# ProDoc_Board1_2026-04-23.net
KiCad netlist of a schematic drawn in EasyEDA Pro
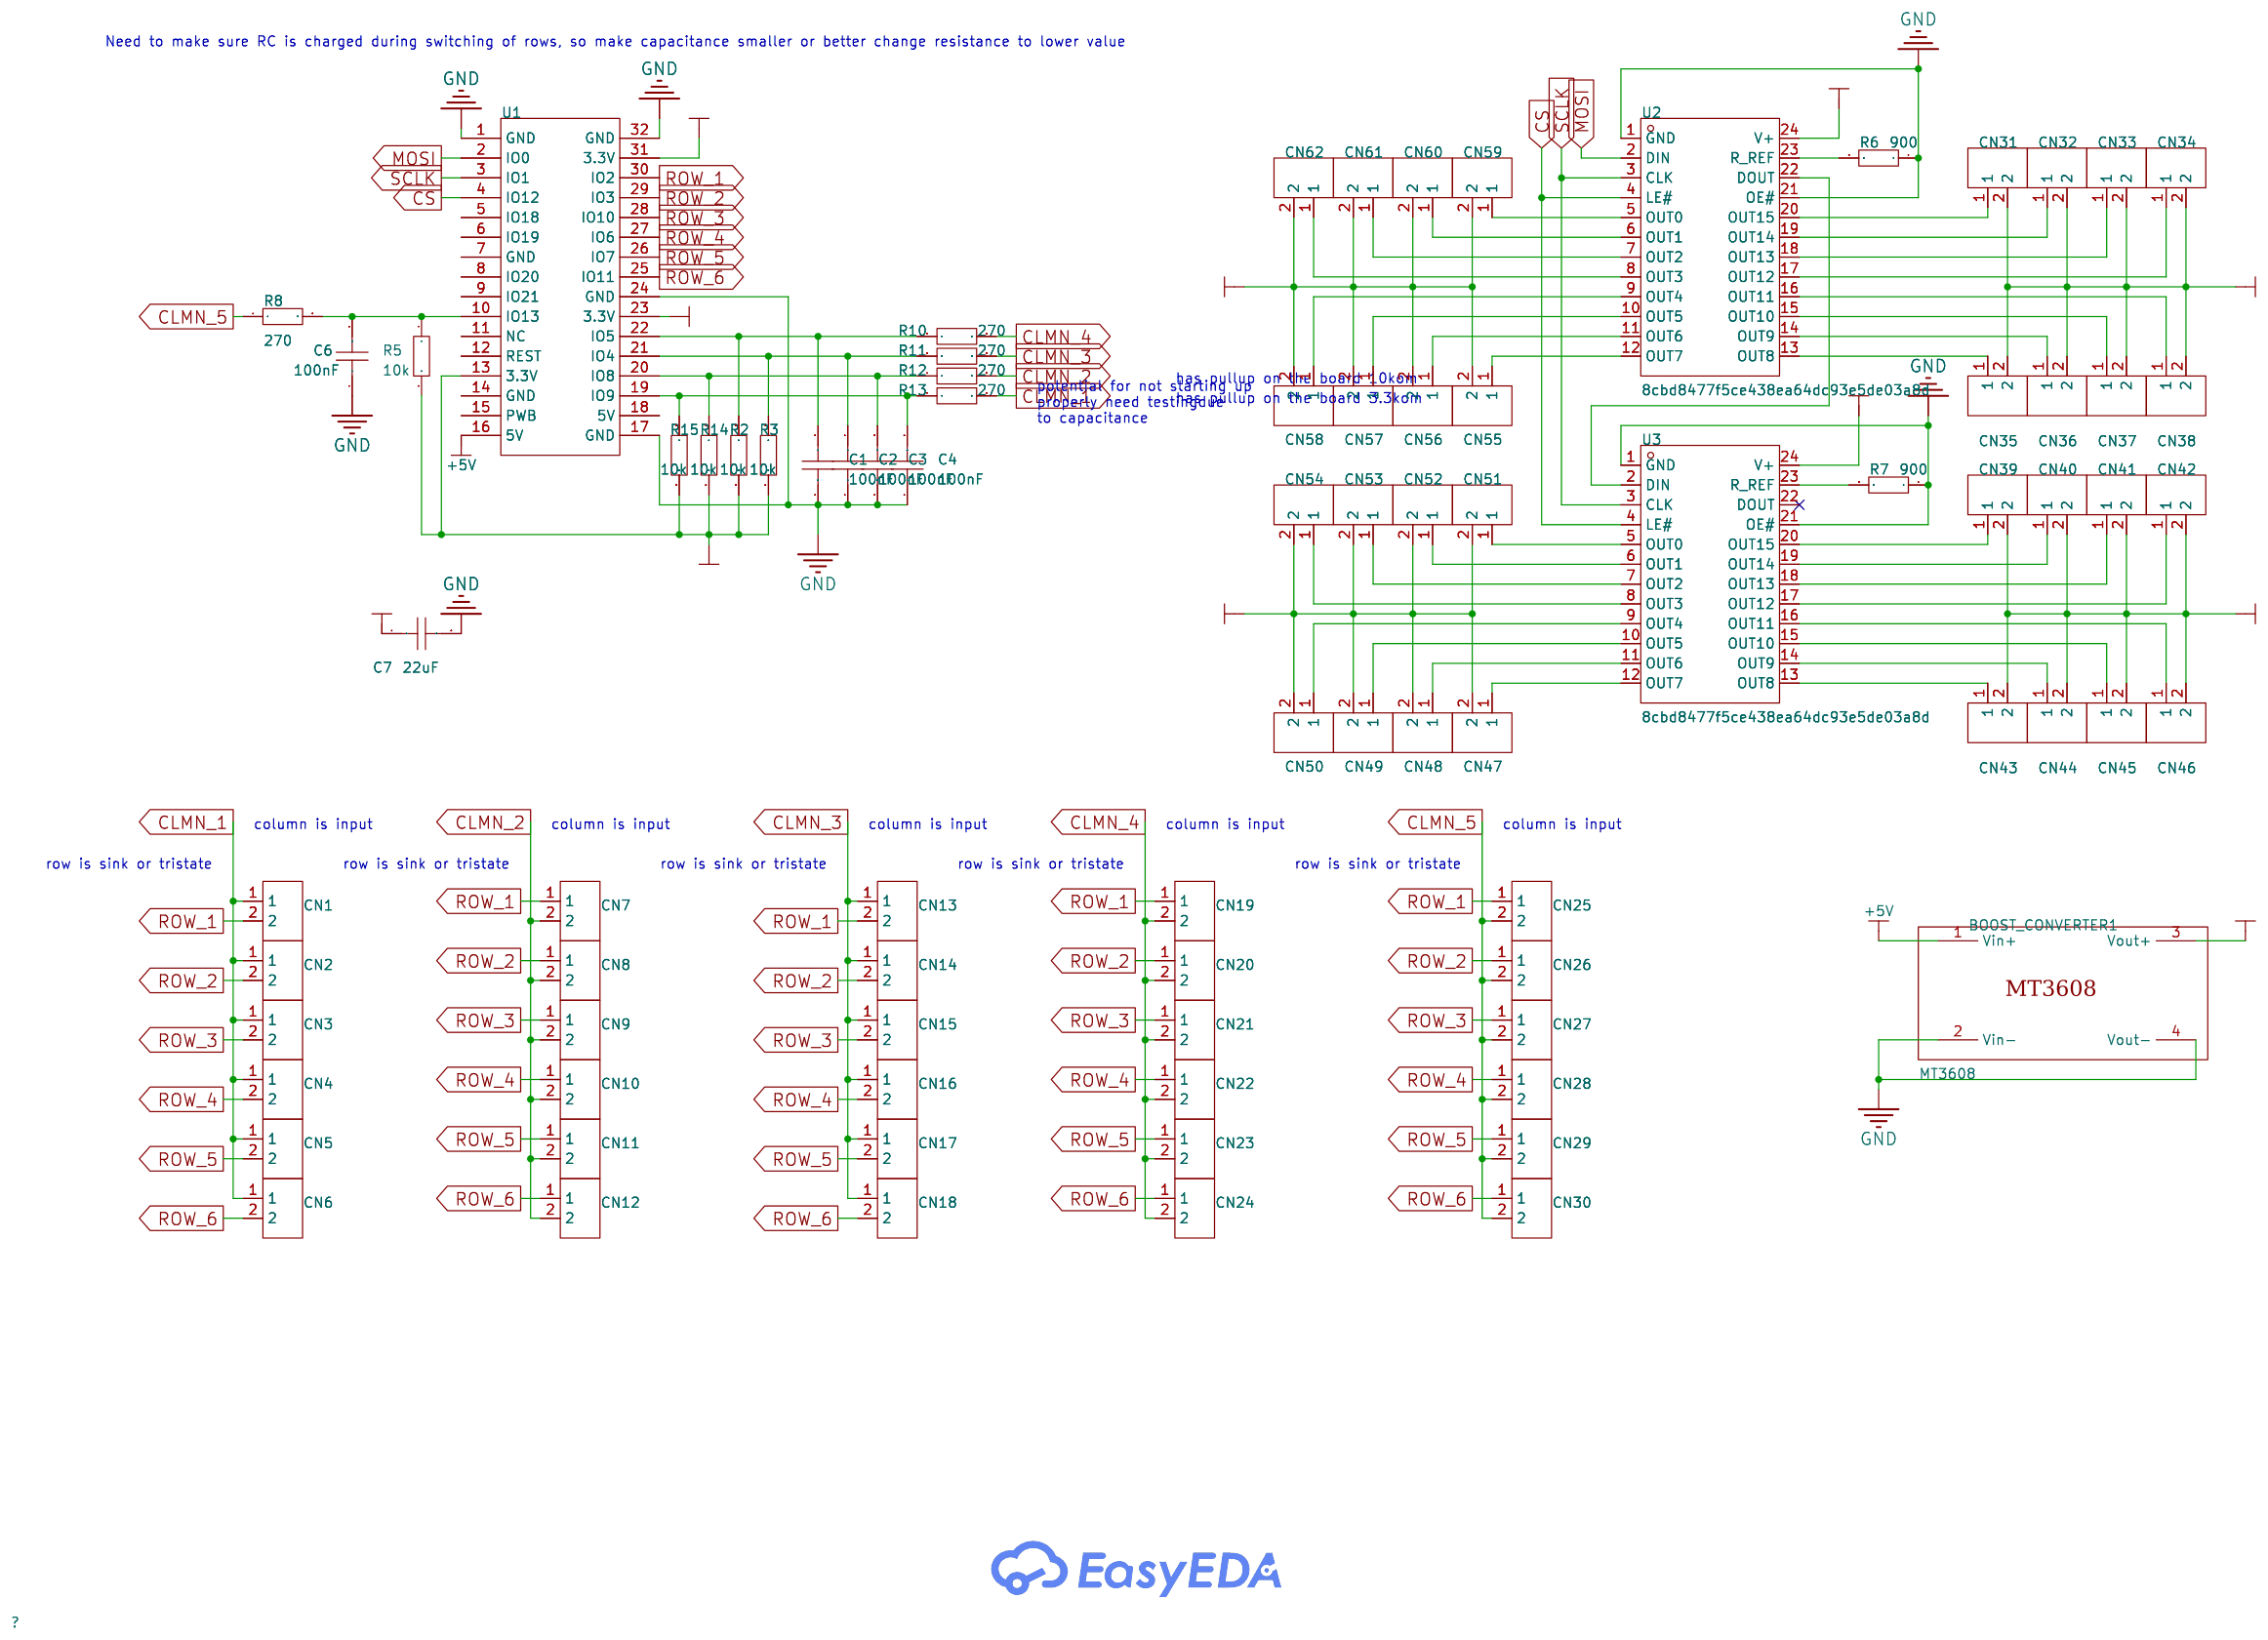
[diagram p0: schematic sheet]

(export (version "E")
  (design (tool "Eeschema 10.0.6"))
  (components
    (comp (ref "BOOST_CONVERTER1")
      (value "MT3608")
      (footprint "easyedapro:MT3608 BOOST")
      (libsource (lib "easyedapro") (part "MT3608"))
    )
    (comp (ref "C1")
      (value "100nF")
      (footprint "easyedapro:CAP-TH_L5.5-W2.4-P5.08-D0.6")
      (fields
        (field (name "Manufacturer Part") "CC1H104ZC1ED3F5O1100")
        (field (name "Manufacturer") "Dersonic(德尔创)")
      )
      (libsource (lib "easyedapro") (part "CC1H104ZC1ED3F5O1100"))
    )
    (comp (ref "C2")
      (value "100nF")
      (footprint "easyedapro:CAP-TH_L5.5-W2.4-P5.08-D0.6")
      (fields
        (field (name "Manufacturer Part") "CC1H104ZC1ED3F5O1100")
        (field (name "Manufacturer") "Dersonic(德尔创)")
      )
      (libsource (lib "easyedapro") (part "CC1H104ZC1ED3F5O1100"))
    )
    (comp (ref "C3")
      (value "100nF")
      (footprint "easyedapro:CAP-TH_L5.5-W2.4-P5.08-D0.6")
      (fields
        (field (name "Manufacturer Part") "CC1H104ZC1ED3F5O1100")
        (field (name "Manufacturer") "Dersonic(德尔创)")
      )
      (libsource (lib "easyedapro") (part "CC1H104ZC1ED3F5O1100"))
    )
    (comp (ref "C4")
      (value "100nF")
      (footprint "easyedapro:CAP-TH_L5.5-W2.4-P5.08-D0.6")
      (fields
        (field (name "Manufacturer Part") "CC1H104ZC1ED3F5O1100")
        (field (name "Manufacturer") "Dersonic(德尔创)")
      )
      (libsource (lib "easyedapro") (part "CC1H104ZC1ED3F5O1100"))
    )
    (comp (ref "C6")
      (value "100nF")
      (footprint "easyedapro:CAP-TH_L5.5-W2.4-P5.08-D0.6")
      (fields
        (field (name "Manufacturer Part") "CC1H104ZC1ED3F5O1100")
        (field (name "Manufacturer") "Dersonic(德尔创)")
      )
      (libsource (lib "easyedapro") (part "CC1H104ZC1ED3F5O1100"))
    )
    (comp (ref "C7")
      (value "22uF")
      (footprint "easyedapro:C1206")
      (description "Capacitance:22uF Tolerance:±10% Tolerance:±10% Voltage Rating:25V Temperature Coefficient:X5R")
      (fields
        (field (name "Manufacturer Part") "FCC1206X226K250HT")
        (field (name "Manufacturer") "FOJAN(富捷)")
      )
      (libsource (lib "easyedapro") (part "FCC1206X226K250HT"))
    )
    (comp (ref "CN1")
      (value "HX-XH2.54-2PZZ")
      (footprint "easyedapro:CONN-TH_2P-P2.50_HX-2.54MM-2P-ZZ-MS")
      (fields (field (name "Manufacturer") "hanxia(韩下)"))
      (libsource (lib "easyedapro") (part "HX-XH2.54-2PZZ"))
    )
    (comp (ref "CN2")
      (value "HX-XH2.54-2PZZ")
      (footprint "easyedapro:CONN-TH_2P-P2.50_HX-2.54MM-2P-ZZ-MS")
      (fields (field (name "Manufacturer") "hanxia(韩下)"))
      (libsource (lib "easyedapro") (part "HX-XH2.54-2PZZ"))
    )
    (comp (ref "CN3")
      (value "HX-XH2.54-2PZZ")
      (footprint "easyedapro:CONN-TH_2P-P2.50_HX-2.54MM-2P-ZZ-MS")
      (fields (field (name "Manufacturer") "hanxia(韩下)"))
      (libsource (lib "easyedapro") (part "HX-XH2.54-2PZZ"))
    )
    (comp (ref "CN4")
      (value "HX-XH2.54-2PZZ")
      (footprint "easyedapro:CONN-TH_2P-P2.50_HX-2.54MM-2P-ZZ-MS")
      (fields (field (name "Manufacturer") "hanxia(韩下)"))
      (libsource (lib "easyedapro") (part "HX-XH2.54-2PZZ"))
    )
    (comp (ref "CN5")
      (value "HX-XH2.54-2PZZ")
      (footprint "easyedapro:CONN-TH_2P-P2.50_HX-2.54MM-2P-ZZ-MS")
      (fields (field (name "Manufacturer") "hanxia(韩下)"))
      (libsource (lib "easyedapro") (part "HX-XH2.54-2PZZ"))
    )
    (comp (ref "CN6")
      (value "HX-XH2.54-2PZZ")
      (footprint "easyedapro:CONN-TH_2P-P2.50_HX-2.54MM-2P-ZZ-MS")
      (fields (field (name "Manufacturer") "hanxia(韩下)"))
      (libsource (lib "easyedapro") (part "HX-XH2.54-2PZZ"))
    )
    (comp (ref "CN7")
      (value "HX-XH2.54-2PZZ")
      (footprint "easyedapro:CONN-TH_2P-P2.50_HX-2.54MM-2P-ZZ-MS")
      (fields (field (name "Manufacturer") "hanxia(韩下)"))
      (libsource (lib "easyedapro") (part "HX-XH2.54-2PZZ"))
    )
    (comp (ref "CN8")
      (value "HX-XH2.54-2PZZ")
      (footprint "easyedapro:CONN-TH_2P-P2.50_HX-2.54MM-2P-ZZ-MS")
      (fields (field (name "Manufacturer") "hanxia(韩下)"))
      (libsource (lib "easyedapro") (part "HX-XH2.54-2PZZ"))
    )
    (comp (ref "CN9")
      (value "HX-XH2.54-2PZZ")
      (footprint "easyedapro:CONN-TH_2P-P2.50_HX-2.54MM-2P-ZZ-MS")
      (fields (field (name "Manufacturer") "hanxia(韩下)"))
      (libsource (lib "easyedapro") (part "HX-XH2.54-2PZZ"))
    )
    (comp (ref "CN10")
      (value "HX-XH2.54-2PZZ")
      (footprint "easyedapro:CONN-TH_2P-P2.50_HX-2.54MM-2P-ZZ-MS")
      (fields (field (name "Manufacturer") "hanxia(韩下)"))
      (libsource (lib "easyedapro") (part "HX-XH2.54-2PZZ"))
    )
    (comp (ref "CN11")
      (value "HX-XH2.54-2PZZ")
      (footprint "easyedapro:CONN-TH_2P-P2.50_HX-2.54MM-2P-ZZ-MS")
      (fields (field (name "Manufacturer") "hanxia(韩下)"))
      (libsource (lib "easyedapro") (part "HX-XH2.54-2PZZ"))
    )
    (comp (ref "CN12")
      (value "HX-XH2.54-2PZZ")
      (footprint "easyedapro:CONN-TH_2P-P2.50_HX-2.54MM-2P-ZZ-MS")
      (fields (field (name "Manufacturer") "hanxia(韩下)"))
      (libsource (lib "easyedapro") (part "HX-XH2.54-2PZZ"))
    )
    (comp (ref "CN13")
      (value "HX-XH2.54-2PZZ")
      (footprint "easyedapro:CONN-TH_2P-P2.50_HX-2.54MM-2P-ZZ-MS")
      (fields (field (name "Manufacturer") "hanxia(韩下)"))
      (libsource (lib "easyedapro") (part "HX-XH2.54-2PZZ"))
    )
    (comp (ref "CN14")
      (value "HX-XH2.54-2PZZ")
      (footprint "easyedapro:CONN-TH_2P-P2.50_HX-2.54MM-2P-ZZ-MS")
      (fields (field (name "Manufacturer") "hanxia(韩下)"))
      (libsource (lib "easyedapro") (part "HX-XH2.54-2PZZ"))
    )
    (comp (ref "CN15")
      (value "HX-XH2.54-2PZZ")
      (footprint "easyedapro:CONN-TH_2P-P2.50_HX-2.54MM-2P-ZZ-MS")
      (fields (field (name "Manufacturer") "hanxia(韩下)"))
      (libsource (lib "easyedapro") (part "HX-XH2.54-2PZZ"))
    )
    (comp (ref "CN16")
      (value "HX-XH2.54-2PZZ")
      (footprint "easyedapro:CONN-TH_2P-P2.50_HX-2.54MM-2P-ZZ-MS")
      (fields (field (name "Manufacturer") "hanxia(韩下)"))
      (libsource (lib "easyedapro") (part "HX-XH2.54-2PZZ"))
    )
    (comp (ref "CN17")
      (value "HX-XH2.54-2PZZ")
      (footprint "easyedapro:CONN-TH_2P-P2.50_HX-2.54MM-2P-ZZ-MS")
      (fields (field (name "Manufacturer") "hanxia(韩下)"))
      (libsource (lib "easyedapro") (part "HX-XH2.54-2PZZ"))
    )
    (comp (ref "CN18")
      (value "HX-XH2.54-2PZZ")
      (footprint "easyedapro:CONN-TH_2P-P2.50_HX-2.54MM-2P-ZZ-MS")
      (fields (field (name "Manufacturer") "hanxia(韩下)"))
      (libsource (lib "easyedapro") (part "HX-XH2.54-2PZZ"))
    )
    (comp (ref "CN19")
      (value "HX-XH2.54-2PZZ")
      (footprint "easyedapro:CONN-TH_2P-P2.50_HX-2.54MM-2P-ZZ-MS")
      (fields (field (name "Manufacturer") "hanxia(韩下)"))
      (libsource (lib "easyedapro") (part "HX-XH2.54-2PZZ"))
    )
    (comp (ref "CN20")
      (value "HX-XH2.54-2PZZ")
      (footprint "easyedapro:CONN-TH_2P-P2.50_HX-2.54MM-2P-ZZ-MS")
      (fields (field (name "Manufacturer") "hanxia(韩下)"))
      (libsource (lib "easyedapro") (part "HX-XH2.54-2PZZ"))
    )
    (comp (ref "CN21")
      (value "HX-XH2.54-2PZZ")
      (footprint "easyedapro:CONN-TH_2P-P2.50_HX-2.54MM-2P-ZZ-MS")
      (fields (field (name "Manufacturer") "hanxia(韩下)"))
      (libsource (lib "easyedapro") (part "HX-XH2.54-2PZZ"))
    )
    (comp (ref "CN22")
      (value "HX-XH2.54-2PZZ")
      (footprint "easyedapro:CONN-TH_2P-P2.50_HX-2.54MM-2P-ZZ-MS")
      (fields (field (name "Manufacturer") "hanxia(韩下)"))
      (libsource (lib "easyedapro") (part "HX-XH2.54-2PZZ"))
    )
    (comp (ref "CN23")
      (value "HX-XH2.54-2PZZ")
      (footprint "easyedapro:CONN-TH_2P-P2.50_HX-2.54MM-2P-ZZ-MS")
      (fields (field (name "Manufacturer") "hanxia(韩下)"))
      (libsource (lib "easyedapro") (part "HX-XH2.54-2PZZ"))
    )
    (comp (ref "CN24")
      (value "HX-XH2.54-2PZZ")
      (footprint "easyedapro:CONN-TH_2P-P2.50_HX-2.54MM-2P-ZZ-MS")
      (fields (field (name "Manufacturer") "hanxia(韩下)"))
      (libsource (lib "easyedapro") (part "HX-XH2.54-2PZZ"))
    )
    (comp (ref "CN25")
      (value "HX-XH2.54-2PZZ")
      (footprint "easyedapro:CONN-TH_2P-P2.50_HX-2.54MM-2P-ZZ-MS")
      (fields (field (name "Manufacturer") "hanxia(韩下)"))
      (libsource (lib "easyedapro") (part "HX-XH2.54-2PZZ"))
    )
    (comp (ref "CN26")
      (value "HX-XH2.54-2PZZ")
      (footprint "easyedapro:CONN-TH_2P-P2.50_HX-2.54MM-2P-ZZ-MS")
      (fields (field (name "Manufacturer") "hanxia(韩下)"))
      (libsource (lib "easyedapro") (part "HX-XH2.54-2PZZ"))
    )
    (comp (ref "CN27")
      (value "HX-XH2.54-2PZZ")
      (footprint "easyedapro:CONN-TH_2P-P2.50_HX-2.54MM-2P-ZZ-MS")
      (fields (field (name "Manufacturer") "hanxia(韩下)"))
      (libsource (lib "easyedapro") (part "HX-XH2.54-2PZZ"))
    )
    (comp (ref "CN28")
      (value "HX-XH2.54-2PZZ")
      (footprint "easyedapro:CONN-TH_2P-P2.50_HX-2.54MM-2P-ZZ-MS")
      (fields (field (name "Manufacturer") "hanxia(韩下)"))
      (libsource (lib "easyedapro") (part "HX-XH2.54-2PZZ"))
    )
    (comp (ref "CN29")
      (value "HX-XH2.54-2PZZ")
      (footprint "easyedapro:CONN-TH_2P-P2.50_HX-2.54MM-2P-ZZ-MS")
      (fields (field (name "Manufacturer") "hanxia(韩下)"))
      (libsource (lib "easyedapro") (part "HX-XH2.54-2PZZ"))
    )
    (comp (ref "CN30")
      (value "HX-XH2.54-2PZZ")
      (footprint "easyedapro:CONN-TH_2P-P2.50_HX-2.54MM-2P-ZZ-MS")
      (fields (field (name "Manufacturer") "hanxia(韩下)"))
      (libsource (lib "easyedapro") (part "HX-XH2.54-2PZZ"))
    )
    (comp (ref "CN31")
      (value "HX-XH2.54-2PZZ")
      (footprint "easyedapro:CONN-TH_2P-P2.50_HX-2.54MM-2P-ZZ-MS")
      (fields (field (name "Manufacturer") "hanxia(韩下)"))
      (libsource (lib "easyedapro") (part "HX-XH2.54-2PZZ"))
    )
    (comp (ref "CN32")
      (value "HX-XH2.54-2PZZ")
      (footprint "easyedapro:CONN-TH_2P-P2.50_HX-2.54MM-2P-ZZ-MS")
      (fields (field (name "Manufacturer") "hanxia(韩下)"))
      (libsource (lib "easyedapro") (part "HX-XH2.54-2PZZ"))
    )
    (comp (ref "CN33")
      (value "HX-XH2.54-2PZZ")
      (footprint "easyedapro:CONN-TH_2P-P2.50_HX-2.54MM-2P-ZZ-MS")
      (fields (field (name "Manufacturer") "hanxia(韩下)"))
      (libsource (lib "easyedapro") (part "HX-XH2.54-2PZZ"))
    )
    (comp (ref "CN34")
      (value "HX-XH2.54-2PZZ")
      (footprint "easyedapro:CONN-TH_2P-P2.50_HX-2.54MM-2P-ZZ-MS")
      (fields (field (name "Manufacturer") "hanxia(韩下)"))
      (libsource (lib "easyedapro") (part "HX-XH2.54-2PZZ"))
    )
    (comp (ref "CN35")
      (value "HX-XH2.54-2PZZ")
      (footprint "easyedapro:CONN-TH_2P-P2.50_HX-2.54MM-2P-ZZ-MS")
      (fields (field (name "Manufacturer") "hanxia(韩下)"))
      (libsource (lib "easyedapro") (part "HX-XH2.54-2PZZ"))
    )
    (comp (ref "CN36")
      (value "HX-XH2.54-2PZZ")
      (footprint "easyedapro:CONN-TH_2P-P2.50_HX-2.54MM-2P-ZZ-MS")
      (fields (field (name "Manufacturer") "hanxia(韩下)"))
      (libsource (lib "easyedapro") (part "HX-XH2.54-2PZZ"))
    )
    (comp (ref "CN37")
      (value "HX-XH2.54-2PZZ")
      (footprint "easyedapro:CONN-TH_2P-P2.50_HX-2.54MM-2P-ZZ-MS")
      (fields (field (name "Manufacturer") "hanxia(韩下)"))
      (libsource (lib "easyedapro") (part "HX-XH2.54-2PZZ"))
    )
    (comp (ref "CN38")
      (value "HX-XH2.54-2PZZ")
      (footprint "easyedapro:CONN-TH_2P-P2.50_HX-2.54MM-2P-ZZ-MS")
      (fields (field (name "Manufacturer") "hanxia(韩下)"))
      (libsource (lib "easyedapro") (part "HX-XH2.54-2PZZ"))
    )
    (comp (ref "CN39")
      (value "HX-XH2.54-2PZZ")
      (footprint "easyedapro:CONN-TH_2P-P2.50_HX-2.54MM-2P-ZZ-MS")
      (fields (field (name "Manufacturer") "hanxia(韩下)"))
      (libsource (lib "easyedapro") (part "HX-XH2.54-2PZZ"))
    )
    (comp (ref "CN40")
      (value "HX-XH2.54-2PZZ")
      (footprint "easyedapro:CONN-TH_2P-P2.50_HX-2.54MM-2P-ZZ-MS")
      (fields (field (name "Manufacturer") "hanxia(韩下)"))
      (libsource (lib "easyedapro") (part "HX-XH2.54-2PZZ"))
    )
    (comp (ref "CN41")
      (value "HX-XH2.54-2PZZ")
      (footprint "easyedapro:CONN-TH_2P-P2.50_HX-2.54MM-2P-ZZ-MS")
      (fields (field (name "Manufacturer") "hanxia(韩下)"))
      (libsource (lib "easyedapro") (part "HX-XH2.54-2PZZ"))
    )
    (comp (ref "CN42")
      (value "HX-XH2.54-2PZZ")
      (footprint "easyedapro:CONN-TH_2P-P2.50_HX-2.54MM-2P-ZZ-MS")
      (fields (field (name "Manufacturer") "hanxia(韩下)"))
      (libsource (lib "easyedapro") (part "HX-XH2.54-2PZZ"))
    )
    (comp (ref "CN43")
      (value "HX-XH2.54-2PZZ")
      (footprint "easyedapro:CONN-TH_2P-P2.50_HX-2.54MM-2P-ZZ-MS")
      (fields (field (name "Manufacturer") "hanxia(韩下)"))
      (libsource (lib "easyedapro") (part "HX-XH2.54-2PZZ"))
    )
    (comp (ref "CN44")
      (value "HX-XH2.54-2PZZ")
      (footprint "easyedapro:CONN-TH_2P-P2.50_HX-2.54MM-2P-ZZ-MS")
      (fields (field (name "Manufacturer") "hanxia(韩下)"))
      (libsource (lib "easyedapro") (part "HX-XH2.54-2PZZ"))
    )
    (comp (ref "CN45")
      (value "HX-XH2.54-2PZZ")
      (footprint "easyedapro:CONN-TH_2P-P2.50_HX-2.54MM-2P-ZZ-MS")
      (fields (field (name "Manufacturer") "hanxia(韩下)"))
      (libsource (lib "easyedapro") (part "HX-XH2.54-2PZZ"))
    )
    (comp (ref "CN46")
      (value "HX-XH2.54-2PZZ")
      (footprint "easyedapro:CONN-TH_2P-P2.50_HX-2.54MM-2P-ZZ-MS")
      (fields (field (name "Manufacturer") "hanxia(韩下)"))
      (libsource (lib "easyedapro") (part "HX-XH2.54-2PZZ"))
    )
    (comp (ref "CN47")
      (value "HX-XH2.54-2PZZ")
      (footprint "easyedapro:CONN-TH_2P-P2.50_HX-2.54MM-2P-ZZ-MS")
      (fields (field (name "Manufacturer") "hanxia(韩下)"))
      (libsource (lib "easyedapro") (part "HX-XH2.54-2PZZ"))
    )
    (comp (ref "CN48")
      (value "HX-XH2.54-2PZZ")
      (footprint "easyedapro:CONN-TH_2P-P2.50_HX-2.54MM-2P-ZZ-MS")
      (fields (field (name "Manufacturer") "hanxia(韩下)"))
      (libsource (lib "easyedapro") (part "HX-XH2.54-2PZZ"))
    )
    (comp (ref "CN49")
      (value "HX-XH2.54-2PZZ")
      (footprint "easyedapro:CONN-TH_2P-P2.50_HX-2.54MM-2P-ZZ-MS")
      (fields (field (name "Manufacturer") "hanxia(韩下)"))
      (libsource (lib "easyedapro") (part "HX-XH2.54-2PZZ"))
    )
    (comp (ref "CN50")
      (value "HX-XH2.54-2PZZ")
      (footprint "easyedapro:CONN-TH_2P-P2.50_HX-2.54MM-2P-ZZ-MS")
      (fields (field (name "Manufacturer") "hanxia(韩下)"))
      (libsource (lib "easyedapro") (part "HX-XH2.54-2PZZ"))
    )
    (comp (ref "CN51")
      (value "HX-XH2.54-2PZZ")
      (footprint "easyedapro:CONN-TH_2P-P2.50_HX-2.54MM-2P-ZZ-MS")
      (fields (field (name "Manufacturer") "hanxia(韩下)"))
      (libsource (lib "easyedapro") (part "HX-XH2.54-2PZZ"))
    )
    (comp (ref "CN52")
      (value "HX-XH2.54-2PZZ")
      (footprint "easyedapro:CONN-TH_2P-P2.50_HX-2.54MM-2P-ZZ-MS")
      (fields (field (name "Manufacturer") "hanxia(韩下)"))
      (libsource (lib "easyedapro") (part "HX-XH2.54-2PZZ"))
    )
    (comp (ref "CN53")
      (value "HX-XH2.54-2PZZ")
      (footprint "easyedapro:CONN-TH_2P-P2.50_HX-2.54MM-2P-ZZ-MS")
      (fields (field (name "Manufacturer") "hanxia(韩下)"))
      (libsource (lib "easyedapro") (part "HX-XH2.54-2PZZ"))
    )
    (comp (ref "CN54")
      (value "HX-XH2.54-2PZZ")
      (footprint "easyedapro:CONN-TH_2P-P2.50_HX-2.54MM-2P-ZZ-MS")
      (fields (field (name "Manufacturer") "hanxia(韩下)"))
      (libsource (lib "easyedapro") (part "HX-XH2.54-2PZZ"))
    )
    (comp (ref "CN55")
      (value "HX-XH2.54-2PZZ")
      (footprint "easyedapro:CONN-TH_2P-P2.50_HX-2.54MM-2P-ZZ-MS")
      (fields (field (name "Manufacturer") "hanxia(韩下)"))
      (libsource (lib "easyedapro") (part "HX-XH2.54-2PZZ"))
    )
    (comp (ref "CN56")
      (value "HX-XH2.54-2PZZ")
      (footprint "easyedapro:CONN-TH_2P-P2.50_HX-2.54MM-2P-ZZ-MS")
      (fields (field (name "Manufacturer") "hanxia(韩下)"))
      (libsource (lib "easyedapro") (part "HX-XH2.54-2PZZ"))
    )
    (comp (ref "CN57")
      (value "HX-XH2.54-2PZZ")
      (footprint "easyedapro:CONN-TH_2P-P2.50_HX-2.54MM-2P-ZZ-MS")
      (fields (field (name "Manufacturer") "hanxia(韩下)"))
      (libsource (lib "easyedapro") (part "HX-XH2.54-2PZZ"))
    )
    (comp (ref "CN58")
      (value "HX-XH2.54-2PZZ")
      (footprint "easyedapro:CONN-TH_2P-P2.50_HX-2.54MM-2P-ZZ-MS")
      (fields (field (name "Manufacturer") "hanxia(韩下)"))
      (libsource (lib "easyedapro") (part "HX-XH2.54-2PZZ"))
    )
    (comp (ref "CN59")
      (value "HX-XH2.54-2PZZ")
      (footprint "easyedapro:CONN-TH_2P-P2.50_HX-2.54MM-2P-ZZ-MS")
      (fields (field (name "Manufacturer") "hanxia(韩下)"))
      (libsource (lib "easyedapro") (part "HX-XH2.54-2PZZ"))
    )
    (comp (ref "CN60")
      (value "HX-XH2.54-2PZZ")
      (footprint "easyedapro:CONN-TH_2P-P2.50_HX-2.54MM-2P-ZZ-MS")
      (fields (field (name "Manufacturer") "hanxia(韩下)"))
      (libsource (lib "easyedapro") (part "HX-XH2.54-2PZZ"))
    )
    (comp (ref "CN61")
      (value "HX-XH2.54-2PZZ")
      (footprint "easyedapro:CONN-TH_2P-P2.50_HX-2.54MM-2P-ZZ-MS")
      (fields (field (name "Manufacturer") "hanxia(韩下)"))
      (libsource (lib "easyedapro") (part "HX-XH2.54-2PZZ"))
    )
    (comp (ref "CN62")
      (value "HX-XH2.54-2PZZ")
      (footprint "easyedapro:CONN-TH_2P-P2.50_HX-2.54MM-2P-ZZ-MS")
      (fields (field (name "Manufacturer") "hanxia(韩下)"))
      (libsource (lib "easyedapro") (part "HX-XH2.54-2PZZ"))
    )
    (comp (ref "R2") (value "10k") (footprint "easyedapro:R0603") (libsource (lib "easyedapro") (part "Res")))
    (comp (ref "R3") (value "10k") (footprint "easyedapro:R0603") (libsource (lib "easyedapro") (part "Res")))
    (comp (ref "R5") (value "10k") (footprint "easyedapro:R0603") (libsource (lib "easyedapro") (part "Res")))
    (comp (ref "R6") (value "900") (footprint "easyedapro:R0603") (libsource (lib "easyedapro") (part "Res")))
    (comp (ref "R7") (value "900") (footprint "easyedapro:R0603") (libsource (lib "easyedapro") (part "Res")))
    (comp (ref "R8") (value "270") (footprint "easyedapro:R0603") (libsource (lib "easyedapro") (part "Res")))
    (comp (ref "R10")
      (value "270")
      (footprint "easyedapro:R0603")
      (libsource (lib "easyedapro") (part "Res"))
    )
    (comp (ref "R11")
      (value "270")
      (footprint "easyedapro:R0603")
      (libsource (lib "easyedapro") (part "Res"))
    )
    (comp (ref "R12")
      (value "270")
      (footprint "easyedapro:R0603")
      (libsource (lib "easyedapro") (part "Res"))
    )
    (comp (ref "R13")
      (value "270")
      (footprint "easyedapro:R0603")
      (libsource (lib "easyedapro") (part "Res"))
    )
    (comp (ref "R14")
      (value "10k")
      (footprint "easyedapro:R0603")
      (libsource (lib "easyedapro") (part "Res"))
    )
    (comp (ref "R15")
      (value "10k")
      (footprint "easyedapro:R0603")
      (libsource (lib "easyedapro") (part "Res"))
    )
    (comp (ref "U1")
      (value "~")
      (footprint "easyedapro:ESP32C3 LUATOS FOOT")
      (libsource (lib "easyedapro") (part "ESP32-C3-LUATOS"))
    )
    (comp (ref "U2")
      (value "8cbd8477f5ce438ea64dc93e5de03a8d")
      (footprint "easyedapro:SOIC-24_L15.4-W7.5-P1.27-LS10.3-BL")
      (libsource (lib "easyedapro") (part "DM135B"))
    )
    (comp (ref "U3")
      (value "8cbd8477f5ce438ea64dc93e5de03a8d")
      (footprint "easyedapro:SOIC-24_L15.4-W7.5-P1.27-LS10.3-BL")
      (libsource (lib "easyedapro") (part "DM135B"))
    )
  )
  (nets
    (net (code "1") (name "+3.3V") (class "Default")
      (node (ref "C7") (pin "1") (pinfunction "1_1") (pintype "unspecified"))
      (node (ref "R14") (pin "2") (pinfunction "2_2") (pintype "input"))
      (node (ref "R15") (pin "2") (pinfunction "2_2") (pintype "input"))
      (node (ref "R2") (pin "2") (pinfunction "2_2") (pintype "input"))
      (node (ref "R3") (pin "2") (pinfunction "2_2") (pintype "input"))
      (node (ref "R5") (pin "2") (pinfunction "2_2") (pintype "input"))
      (node (ref "U1") (pin "13") (pinfunction "3.3V_13") (pintype "input"))
      (node (ref "U1") (pin "23") (pinfunction "3.3V_23") (pintype "input"))
      (node (ref "U1") (pin "31") (pinfunction "3.3V_31") (pintype "input"))
      (node (ref "U2") (pin "24") (pinfunction "V+_24") (pintype "unspecified"))
      (node (ref "U3") (pin "24") (pinfunction "V+_24") (pintype "unspecified"))
    )
    (net (code "2") (name "+5V") (class "Default")
      (node (ref "BOOST_CONVERTER1") (pin "1") (pinfunction "Vin+_1") (pintype "input"))
      (node (ref "U1") (pin "16") (pinfunction "5V_16") (pintype "input"))
    )
    (net (code "3") (name "+12V") (class "Default")
      (node (ref "BOOST_CONVERTER1") (pin "3") (pinfunction "Vout+_3") (pintype "input"))
      (node (ref "CN31") (pin "2") (pinfunction "2_2") (pintype "unspecified"))
      (node (ref "CN32") (pin "2") (pinfunction "2_2") (pintype "unspecified"))
      (node (ref "CN33") (pin "2") (pinfunction "2_2") (pintype "unspecified"))
      (node (ref "CN34") (pin "2") (pinfunction "2_2") (pintype "unspecified"))
      (node (ref "CN35") (pin "2") (pinfunction "2_2") (pintype "unspecified"))
      (node (ref "CN36") (pin "2") (pinfunction "2_2") (pintype "unspecified"))
      (node (ref "CN37") (pin "2") (pinfunction "2_2") (pintype "unspecified"))
      (node (ref "CN38") (pin "2") (pinfunction "2_2") (pintype "unspecified"))
      (node (ref "CN39") (pin "2") (pinfunction "2_2") (pintype "unspecified"))
      (node (ref "CN40") (pin "2") (pinfunction "2_2") (pintype "unspecified"))
      (node (ref "CN41") (pin "2") (pinfunction "2_2") (pintype "unspecified"))
      (node (ref "CN42") (pin "2") (pinfunction "2_2") (pintype "unspecified"))
      (node (ref "CN43") (pin "2") (pinfunction "2_2") (pintype "unspecified"))
      (node (ref "CN44") (pin "2") (pinfunction "2_2") (pintype "unspecified"))
      (node (ref "CN45") (pin "2") (pinfunction "2_2") (pintype "unspecified"))
      (node (ref "CN46") (pin "2") (pinfunction "2_2") (pintype "unspecified"))
      (node (ref "CN47") (pin "2") (pinfunction "2_2") (pintype "unspecified"))
      (node (ref "CN48") (pin "2") (pinfunction "2_2") (pintype "unspecified"))
      (node (ref "CN49") (pin "2") (pinfunction "2_2") (pintype "unspecified"))
      (node (ref "CN50") (pin "2") (pinfunction "2_2") (pintype "unspecified"))
      (node (ref "CN51") (pin "2") (pinfunction "2_2") (pintype "unspecified"))
      (node (ref "CN52") (pin "2") (pinfunction "2_2") (pintype "unspecified"))
      (node (ref "CN53") (pin "2") (pinfunction "2_2") (pintype "unspecified"))
      (node (ref "CN54") (pin "2") (pinfunction "2_2") (pintype "unspecified"))
      (node (ref "CN55") (pin "2") (pinfunction "2_2") (pintype "unspecified"))
      (node (ref "CN56") (pin "2") (pinfunction "2_2") (pintype "unspecified"))
      (node (ref "CN57") (pin "2") (pinfunction "2_2") (pintype "unspecified"))
      (node (ref "CN58") (pin "2") (pinfunction "2_2") (pintype "unspecified"))
      (node (ref "CN59") (pin "2") (pinfunction "2_2") (pintype "unspecified"))
      (node (ref "CN60") (pin "2") (pinfunction "2_2") (pintype "unspecified"))
      (node (ref "CN61") (pin "2") (pinfunction "2_2") (pintype "unspecified"))
      (node (ref "CN62") (pin "2") (pinfunction "2_2") (pintype "unspecified"))
    )
    (net (code "4") (name "CLMN_1") (class "Default")
      (node (ref "CN1") (pin "1") (pinfunction "1_1") (pintype "unspecified"))
      (node (ref "CN2") (pin "1") (pinfunction "1_1") (pintype "unspecified"))
      (node (ref "CN3") (pin "1") (pinfunction "1_1") (pintype "unspecified"))
      (node (ref "CN4") (pin "1") (pinfunction "1_1") (pintype "unspecified"))
      (node (ref "CN5") (pin "1") (pinfunction "1_1") (pintype "unspecified"))
      (node (ref "CN6") (pin "1") (pinfunction "1_1") (pintype "unspecified"))
      (node (ref "R13") (pin "2") (pinfunction "2_2") (pintype "input"))
    )
    (net (code "5") (name "CLMN_2") (class "Default")
      (node (ref "CN10") (pin "2") (pinfunction "2_2") (pintype "unspecified"))
      (node (ref "CN11") (pin "2") (pinfunction "2_2") (pintype "unspecified"))
      (node (ref "CN12") (pin "2") (pinfunction "2_2") (pintype "unspecified"))
      (node (ref "CN7") (pin "2") (pinfunction "2_2") (pintype "unspecified"))
      (node (ref "CN8") (pin "2") (pinfunction "2_2") (pintype "unspecified"))
      (node (ref "CN9") (pin "2") (pinfunction "2_2") (pintype "unspecified"))
      (node (ref "R12") (pin "2") (pinfunction "2_2") (pintype "input"))
    )
    (net (code "6") (name "CLMN_3") (class "Default")
      (node (ref "CN13") (pin "1") (pinfunction "1_1") (pintype "unspecified"))
      (node (ref "CN14") (pin "1") (pinfunction "1_1") (pintype "unspecified"))
      (node (ref "CN15") (pin "1") (pinfunction "1_1") (pintype "unspecified"))
      (node (ref "CN16") (pin "1") (pinfunction "1_1") (pintype "unspecified"))
      (node (ref "CN17") (pin "1") (pinfunction "1_1") (pintype "unspecified"))
      (node (ref "CN18") (pin "1") (pinfunction "1_1") (pintype "unspecified"))
      (node (ref "R11") (pin "2") (pinfunction "2_2") (pintype "input"))
    )
    (net (code "7") (name "CLMN_4") (class "Default")
      (node (ref "CN19") (pin "2") (pinfunction "2_2") (pintype "unspecified"))
      (node (ref "CN20") (pin "2") (pinfunction "2_2") (pintype "unspecified"))
      (node (ref "CN21") (pin "2") (pinfunction "2_2") (pintype "unspecified"))
      (node (ref "CN22") (pin "2") (pinfunction "2_2") (pintype "unspecified"))
      (node (ref "CN23") (pin "2") (pinfunction "2_2") (pintype "unspecified"))
      (node (ref "CN24") (pin "2") (pinfunction "2_2") (pintype "unspecified"))
      (node (ref "R10") (pin "2") (pinfunction "2_2") (pintype "input"))
    )
    (net (code "8") (name "CLMN_5") (class "Default")
      (node (ref "CN25") (pin "2") (pinfunction "2_2") (pintype "unspecified"))
      (node (ref "CN26") (pin "2") (pinfunction "2_2") (pintype "unspecified"))
      (node (ref "CN27") (pin "2") (pinfunction "2_2") (pintype "unspecified"))
      (node (ref "CN28") (pin "2") (pinfunction "2_2") (pintype "unspecified"))
      (node (ref "CN29") (pin "2") (pinfunction "2_2") (pintype "unspecified"))
      (node (ref "CN30") (pin "2") (pinfunction "2_2") (pintype "unspecified"))
      (node (ref "R8") (pin "1") (pinfunction "1_1") (pintype "input"))
    )
    (net (code "9") (name "CS") (class "Default")
      (node (ref "U1") (pin "4") (pinfunction "IO12_4") (pintype "input"))
      (node (ref "U2") (pin "4") (pinfunction "LE#_4") (pintype "unspecified"))
      (node (ref "U3") (pin "4") (pinfunction "LE#_4") (pintype "unspecified"))
    )
    (net (code "10") (name "GND") (class "Default")
      (node (ref "BOOST_CONVERTER1") (pin "2") (pinfunction "Vin-_2") (pintype "input"))
      (node (ref "BOOST_CONVERTER1") (pin "4") (pinfunction "Vout-_4") (pintype "input"))
      (node (ref "C1") (pin "1") (pinfunction "1_1") (pintype "unspecified"))
      (node (ref "C2") (pin "1") (pinfunction "1_1") (pintype "unspecified"))
      (node (ref "C3") (pin "1") (pinfunction "1_1") (pintype "unspecified"))
      (node (ref "C4") (pin "1") (pinfunction "1_1") (pintype "unspecified"))
      (node (ref "C6") (pin "1") (pinfunction "1_1") (pintype "unspecified"))
      (node (ref "C7") (pin "2") (pinfunction "2_2") (pintype "unspecified"))
      (node (ref "R6") (pin "1") (pinfunction "1_1") (pintype "input"))
      (node (ref "R7") (pin "1") (pinfunction "1_1") (pintype "input"))
      (node (ref "U1") (pin "1") (pinfunction "GND_1") (pintype "input"))
      (node (ref "U1") (pin "17") (pinfunction "GND_17") (pintype "input"))
      (node (ref "U1") (pin "24") (pinfunction "GND_24") (pintype "input"))
      (node (ref "U1") (pin "32") (pinfunction "GND_32") (pintype "input"))
      (node (ref "U2") (pin "1") (pinfunction "GND_1") (pintype "unspecified"))
      (node (ref "U2") (pin "21") (pinfunction "OE#_21") (pintype "unspecified"))
      (node (ref "U3") (pin "1") (pinfunction "GND_1") (pintype "unspecified"))
      (node (ref "U3") (pin "21") (pinfunction "OE#_21") (pintype "unspecified"))
    )
    (net (code "11") (name "MOSI") (class "Default")
      (node (ref "U1") (pin "2") (pinfunction "IO0_2") (pintype "input"))
      (node (ref "U2") (pin "2") (pinfunction "DIN_2") (pintype "unspecified"))
    )
    (net (code "12") (name "Net-(U1-IO4)") (class "Default")
      (node (ref "C2") (pin "2") (pinfunction "2_2") (pintype "unspecified"))
      (node (ref "R11") (pin "1") (pinfunction "1_1") (pintype "input"))
      (node (ref "R3") (pin "1") (pinfunction "1_1") (pintype "input"))
      (node (ref "U1") (pin "21") (pinfunction "IO4_21") (pintype "input"))
    )
    (net (code "13") (name "Net-(U1-IO5)") (class "Default")
      (node (ref "C1") (pin "2") (pinfunction "2_2") (pintype "unspecified"))
      (node (ref "R10") (pin "1") (pinfunction "1_1") (pintype "input"))
      (node (ref "R2") (pin "1") (pinfunction "1_1") (pintype "input"))
      (node (ref "U1") (pin "22") (pinfunction "IO5_22") (pintype "input"))
    )
    (net (code "14") (name "Net-(U1-IO8)") (class "Default")
      (node (ref "C3") (pin "2") (pinfunction "2_2") (pintype "unspecified"))
      (node (ref "R12") (pin "1") (pinfunction "1_1") (pintype "input"))
      (node (ref "R14") (pin "1") (pinfunction "1_1") (pintype "input"))
      (node (ref "U1") (pin "20") (pinfunction "IO8_20") (pintype "input"))
    )
    (net (code "15") (name "Net-(U1-IO9)") (class "Default")
      (node (ref "C4") (pin "2") (pinfunction "2_2") (pintype "unspecified"))
      (node (ref "R13") (pin "1") (pinfunction "1_1") (pintype "input"))
      (node (ref "R15") (pin "1") (pinfunction "1_1") (pintype "input"))
      (node (ref "U1") (pin "19") (pinfunction "IO9_19") (pintype "input"))
    )
    (net (code "16") (name "Net-(U1-IO13)") (class "Default")
      (node (ref "C6") (pin "2") (pinfunction "2_2") (pintype "unspecified"))
      (node (ref "R5") (pin "1") (pinfunction "1_1") (pintype "input"))
      (node (ref "R8") (pin "2") (pinfunction "2_2") (pintype "input"))
      (node (ref "U1") (pin "10") (pinfunction "IO13_10") (pintype "input"))
    )
    (net (code "17") (name "Net-(U2-DOUT)") (class "Default")
      (node (ref "U2") (pin "22") (pinfunction "DOUT_22") (pintype "unspecified"))
      (node (ref "U3") (pin "2") (pinfunction "DIN_2") (pintype "unspecified"))
    )
    (net (code "18") (name "Net-(U2-OUT0)") (class "Default")
      (node (ref "CN59") (pin "1") (pinfunction "1_1") (pintype "unspecified"))
      (node (ref "U2") (pin "5") (pinfunction "OUT0_5") (pintype "unspecified"))
    )
    (net (code "19") (name "Net-(U2-OUT1)") (class "Default")
      (node (ref "CN60") (pin "1") (pinfunction "1_1") (pintype "unspecified"))
      (node (ref "U2") (pin "6") (pinfunction "OUT1_6") (pintype "unspecified"))
    )
    (net (code "20") (name "Net-(U2-OUT2)") (class "Default")
      (node (ref "CN61") (pin "1") (pinfunction "1_1") (pintype "unspecified"))
      (node (ref "U2") (pin "7") (pinfunction "OUT2_7") (pintype "unspecified"))
    )
    (net (code "21") (name "Net-(U2-OUT3)") (class "Default")
      (node (ref "CN62") (pin "1") (pinfunction "1_1") (pintype "unspecified"))
      (node (ref "U2") (pin "8") (pinfunction "OUT3_8") (pintype "unspecified"))
    )
    (net (code "22") (name "Net-(U2-OUT4)") (class "Default")
      (node (ref "CN58") (pin "1") (pinfunction "1_1") (pintype "unspecified"))
      (node (ref "U2") (pin "9") (pinfunction "OUT4_9") (pintype "unspecified"))
    )
    (net (code "23") (name "Net-(U2-OUT5)") (class "Default")
      (node (ref "CN57") (pin "1") (pinfunction "1_1") (pintype "unspecified"))
      (node (ref "U2") (pin "10") (pinfunction "OUT5_10") (pintype "unspecified"))
    )
    (net (code "24") (name "Net-(U2-OUT6)") (class "Default")
      (node (ref "CN56") (pin "1") (pinfunction "1_1") (pintype "unspecified"))
      (node (ref "U2") (pin "11") (pinfunction "OUT6_11") (pintype "unspecified"))
    )
    (net (code "25") (name "Net-(U2-OUT7)") (class "Default")
      (node (ref "CN55") (pin "1") (pinfunction "1_1") (pintype "unspecified"))
      (node (ref "U2") (pin "12") (pinfunction "OUT7_12") (pintype "unspecified"))
    )
    (net (code "26") (name "Net-(U2-OUT8)") (class "Default")
      (node (ref "CN35") (pin "1") (pinfunction "1_1") (pintype "unspecified"))
      (node (ref "U2") (pin "13") (pinfunction "OUT8_13") (pintype "unspecified"))
    )
    (net (code "27") (name "Net-(U2-OUT9)") (class "Default")
      (node (ref "CN36") (pin "1") (pinfunction "1_1") (pintype "unspecified"))
      (node (ref "U2") (pin "14") (pinfunction "OUT9_14") (pintype "unspecified"))
    )
    (net (code "28") (name "Net-(U2-OUT10)") (class "Default")
      (node (ref "CN37") (pin "1") (pinfunction "1_1") (pintype "unspecified"))
      (node (ref "U2") (pin "15") (pinfunction "OUT10_15") (pintype "unspecified"))
    )
    (net (code "29") (name "Net-(U2-OUT11)") (class "Default")
      (node (ref "CN38") (pin "1") (pinfunction "1_1") (pintype "unspecified"))
      (node (ref "U2") (pin "16") (pinfunction "OUT11_16") (pintype "unspecified"))
    )
    (net (code "30") (name "Net-(U2-OUT12)") (class "Default")
      (node (ref "CN34") (pin "1") (pinfunction "1_1") (pintype "unspecified"))
      (node (ref "U2") (pin "17") (pinfunction "OUT12_17") (pintype "unspecified"))
    )
    (net (code "31") (name "Net-(U2-OUT13)") (class "Default")
      (node (ref "CN33") (pin "1") (pinfunction "1_1") (pintype "unspecified"))
      (node (ref "U2") (pin "18") (pinfunction "OUT13_18") (pintype "unspecified"))
    )
    (net (code "32") (name "Net-(U2-OUT14)") (class "Default")
      (node (ref "CN32") (pin "1") (pinfunction "1_1") (pintype "unspecified"))
      (node (ref "U2") (pin "19") (pinfunction "OUT14_19") (pintype "unspecified"))
    )
    (net (code "33") (name "Net-(U2-OUT15)") (class "Default")
      (node (ref "CN31") (pin "1") (pinfunction "1_1") (pintype "unspecified"))
      (node (ref "U2") (pin "20") (pinfunction "OUT15_20") (pintype "unspecified"))
    )
    (net (code "34") (name "Net-(U2-R_REF)") (class "Default")
      (node (ref "R6") (pin "2") (pinfunction "2_2") (pintype "input"))
      (node (ref "U2") (pin "23") (pinfunction "R_REF_23") (pintype "unspecified"))
    )
    (net (code "35") (name "Net-(U3-OUT0)") (class "Default")
      (node (ref "CN51") (pin "1") (pinfunction "1_1") (pintype "unspecified"))
      (node (ref "U3") (pin "5") (pinfunction "OUT0_5") (pintype "unspecified"))
    )
    (net (code "36") (name "Net-(U3-OUT1)") (class "Default")
      (node (ref "CN52") (pin "1") (pinfunction "1_1") (pintype "unspecified"))
      (node (ref "U3") (pin "6") (pinfunction "OUT1_6") (pintype "unspecified"))
    )
    (net (code "37") (name "Net-(U3-OUT2)") (class "Default")
      (node (ref "CN53") (pin "1") (pinfunction "1_1") (pintype "unspecified"))
      (node (ref "U3") (pin "7") (pinfunction "OUT2_7") (pintype "unspecified"))
    )
    (net (code "38") (name "Net-(U3-OUT3)") (class "Default")
      (node (ref "CN54") (pin "1") (pinfunction "1_1") (pintype "unspecified"))
      (node (ref "U3") (pin "8") (pinfunction "OUT3_8") (pintype "unspecified"))
    )
    (net (code "39") (name "Net-(U3-OUT4)") (class "Default")
      (node (ref "CN50") (pin "1") (pinfunction "1_1") (pintype "unspecified"))
      (node (ref "U3") (pin "9") (pinfunction "OUT4_9") (pintype "unspecified"))
    )
    (net (code "40") (name "Net-(U3-OUT5)") (class "Default")
      (node (ref "CN49") (pin "1") (pinfunction "1_1") (pintype "unspecified"))
      (node (ref "U3") (pin "10") (pinfunction "OUT5_10") (pintype "unspecified"))
    )
    (net (code "41") (name "Net-(U3-OUT6)") (class "Default")
      (node (ref "CN48") (pin "1") (pinfunction "1_1") (pintype "unspecified"))
      (node (ref "U3") (pin "11") (pinfunction "OUT6_11") (pintype "unspecified"))
    )
    (net (code "42") (name "Net-(U3-OUT7)") (class "Default")
      (node (ref "CN47") (pin "1") (pinfunction "1_1") (pintype "unspecified"))
      (node (ref "U3") (pin "12") (pinfunction "OUT7_12") (pintype "unspecified"))
    )
    (net (code "43") (name "Net-(U3-OUT8)") (class "Default")
      (node (ref "CN43") (pin "1") (pinfunction "1_1") (pintype "unspecified"))
      (node (ref "U3") (pin "13") (pinfunction "OUT8_13") (pintype "unspecified"))
    )
    (net (code "44") (name "Net-(U3-OUT9)") (class "Default")
      (node (ref "CN44") (pin "1") (pinfunction "1_1") (pintype "unspecified"))
      (node (ref "U3") (pin "14") (pinfunction "OUT9_14") (pintype "unspecified"))
    )
    (net (code "45") (name "Net-(U3-OUT10)") (class "Default")
      (node (ref "CN45") (pin "1") (pinfunction "1_1") (pintype "unspecified"))
      (node (ref "U3") (pin "15") (pinfunction "OUT10_15") (pintype "unspecified"))
    )
    (net (code "46") (name "Net-(U3-OUT11)") (class "Default")
      (node (ref "CN46") (pin "1") (pinfunction "1_1") (pintype "unspecified"))
      (node (ref "U3") (pin "16") (pinfunction "OUT11_16") (pintype "unspecified"))
    )
    (net (code "47") (name "Net-(U3-OUT12)") (class "Default")
      (node (ref "CN42") (pin "1") (pinfunction "1_1") (pintype "unspecified"))
      (node (ref "U3") (pin "17") (pinfunction "OUT12_17") (pintype "unspecified"))
    )
    (net (code "48") (name "Net-(U3-OUT13)") (class "Default")
      (node (ref "CN41") (pin "1") (pinfunction "1_1") (pintype "unspecified"))
      (node (ref "U3") (pin "18") (pinfunction "OUT13_18") (pintype "unspecified"))
    )
    (net (code "49") (name "Net-(U3-OUT14)") (class "Default")
      (node (ref "CN40") (pin "1") (pinfunction "1_1") (pintype "unspecified"))
      (node (ref "U3") (pin "19") (pinfunction "OUT14_19") (pintype "unspecified"))
    )
    (net (code "50") (name "Net-(U3-OUT15)") (class "Default")
      (node (ref "CN39") (pin "1") (pinfunction "1_1") (pintype "unspecified"))
      (node (ref "U3") (pin "20") (pinfunction "OUT15_20") (pintype "unspecified"))
    )
    (net (code "51") (name "Net-(U3-R_REF)") (class "Default")
      (node (ref "R7") (pin "2") (pinfunction "2_2") (pintype "input"))
      (node (ref "U3") (pin "23") (pinfunction "R_REF_23") (pintype "unspecified"))
    )
    (net (code "52") (name "ROW_1") (class "Default")
      (node (ref "CN1") (pin "2") (pinfunction "2_2") (pintype "unspecified"))
      (node (ref "CN13") (pin "2") (pinfunction "2_2") (pintype "unspecified"))
      (node (ref "CN19") (pin "1") (pinfunction "1_1") (pintype "unspecified"))
      (node (ref "CN25") (pin "1") (pinfunction "1_1") (pintype "unspecified"))
      (node (ref "CN7") (pin "1") (pinfunction "1_1") (pintype "unspecified"))
      (node (ref "U1") (pin "30") (pinfunction "IO2_30") (pintype "input"))
    )
    (net (code "53") (name "ROW_2") (class "Default")
      (node (ref "CN14") (pin "2") (pinfunction "2_2") (pintype "unspecified"))
      (node (ref "CN2") (pin "2") (pinfunction "2_2") (pintype "unspecified"))
      (node (ref "CN20") (pin "1") (pinfunction "1_1") (pintype "unspecified"))
      (node (ref "CN26") (pin "1") (pinfunction "1_1") (pintype "unspecified"))
      (node (ref "CN8") (pin "1") (pinfunction "1_1") (pintype "unspecified"))
      (node (ref "U1") (pin "29") (pinfunction "IO3_29") (pintype "input"))
    )
    (net (code "54") (name "ROW_3") (class "Default")
      (node (ref "CN15") (pin "2") (pinfunction "2_2") (pintype "unspecified"))
      (node (ref "CN21") (pin "1") (pinfunction "1_1") (pintype "unspecified"))
      (node (ref "CN27") (pin "1") (pinfunction "1_1") (pintype "unspecified"))
      (node (ref "CN3") (pin "2") (pinfunction "2_2") (pintype "unspecified"))
      (node (ref "CN9") (pin "1") (pinfunction "1_1") (pintype "unspecified"))
      (node (ref "U1") (pin "28") (pinfunction "IO10_28") (pintype "input"))
    )
    (net (code "55") (name "ROW_4") (class "Default")
      (node (ref "CN10") (pin "1") (pinfunction "1_1") (pintype "unspecified"))
      (node (ref "CN16") (pin "2") (pinfunction "2_2") (pintype "unspecified"))
      (node (ref "CN22") (pin "1") (pinfunction "1_1") (pintype "unspecified"))
      (node (ref "CN28") (pin "1") (pinfunction "1_1") (pintype "unspecified"))
      (node (ref "CN4") (pin "2") (pinfunction "2_2") (pintype "unspecified"))
      (node (ref "U1") (pin "27") (pinfunction "IO6_27") (pintype "input"))
    )
    (net (code "56") (name "ROW_5") (class "Default")
      (node (ref "CN11") (pin "1") (pinfunction "1_1") (pintype "unspecified"))
      (node (ref "CN17") (pin "2") (pinfunction "2_2") (pintype "unspecified"))
      (node (ref "CN23") (pin "1") (pinfunction "1_1") (pintype "unspecified"))
      (node (ref "CN29") (pin "1") (pinfunction "1_1") (pintype "unspecified"))
      (node (ref "CN5") (pin "2") (pinfunction "2_2") (pintype "unspecified"))
      (node (ref "U1") (pin "26") (pinfunction "IO7_26") (pintype "input"))
    )
    (net (code "57") (name "ROW_6") (class "Default")
      (node (ref "CN12") (pin "1") (pinfunction "1_1") (pintype "unspecified"))
      (node (ref "CN18") (pin "2") (pinfunction "2_2") (pintype "unspecified"))
      (node (ref "CN24") (pin "1") (pinfunction "1_1") (pintype "unspecified"))
      (node (ref "CN30") (pin "1") (pinfunction "1_1") (pintype "unspecified"))
      (node (ref "CN6") (pin "2") (pinfunction "2_2") (pintype "unspecified"))
      (node (ref "U1") (pin "25") (pinfunction "IO11_25") (pintype "input"))
    )
    (net (code "58") (name "SCLK") (class "Default")
      (node (ref "U1") (pin "3") (pinfunction "IO1_3") (pintype "input"))
      (node (ref "U2") (pin "3") (pinfunction "CLK_3") (pintype "unspecified"))
      (node (ref "U3") (pin "3") (pinfunction "CLK_3") (pintype "unspecified"))
    )
    (net (code "59") (name "unconnected-(U1-5V-Pad18)") (class "Default")
      (node (ref "U1") (pin "18") (pinfunction "5V_18") (pintype "input"))
    )
    (net (code "60") (name "unconnected-(U1-GND-Pad7)") (class "Default")
      (node (ref "U1") (pin "7") (pinfunction "GND_7") (pintype "input"))
    )
    (net (code "61") (name "unconnected-(U1-GND-Pad14)") (class "Default")
      (node (ref "U1") (pin "14") (pinfunction "GND_14") (pintype "input"))
    )
    (net (code "62") (name "unconnected-(U1-IO18-Pad5)") (class "Default")
      (node (ref "U1") (pin "5") (pinfunction "IO18_5") (pintype "input"))
    )
    (net (code "63") (name "unconnected-(U1-IO19-Pad6)") (class "Default")
      (node (ref "U1") (pin "6") (pinfunction "IO19_6") (pintype "input"))
    )
    (net (code "64") (name "unconnected-(U1-IO20-Pad8)") (class "Default")
      (node (ref "U1") (pin "8") (pinfunction "IO20_8") (pintype "input"))
    )
    (net (code "65") (name "unconnected-(U1-IO21-Pad9)") (class "Default")
      (node (ref "U1") (pin "9") (pinfunction "IO21_9") (pintype "input"))
    )
    (net (code "66") (name "unconnected-(U1-NC-Pad11)") (class "Default")
      (node (ref "U1") (pin "11") (pinfunction "NC_11") (pintype "input"))
    )
    (net (code "67") (name "unconnected-(U1-PWB-Pad15)") (class "Default")
      (node (ref "U1") (pin "15") (pinfunction "PWB_15") (pintype "input"))
    )
    (net (code "68") (name "unconnected-(U1-REST-Pad12)") (class "Default")
      (node (ref "U1") (pin "12") (pinfunction "REST_12") (pintype "input"))
    )
    (net (code "69") (name "unconnected-(U3-DOUT-Pad22)") (class "Default")
      (node (ref "U3") (pin "22") (pinfunction "DOUT_22") (pintype "unspecified+no_connect"))
    )
  )
)
